# BYPASS_BLOCK.net
KiCad netlist of a schematic drawn in Altium Designer
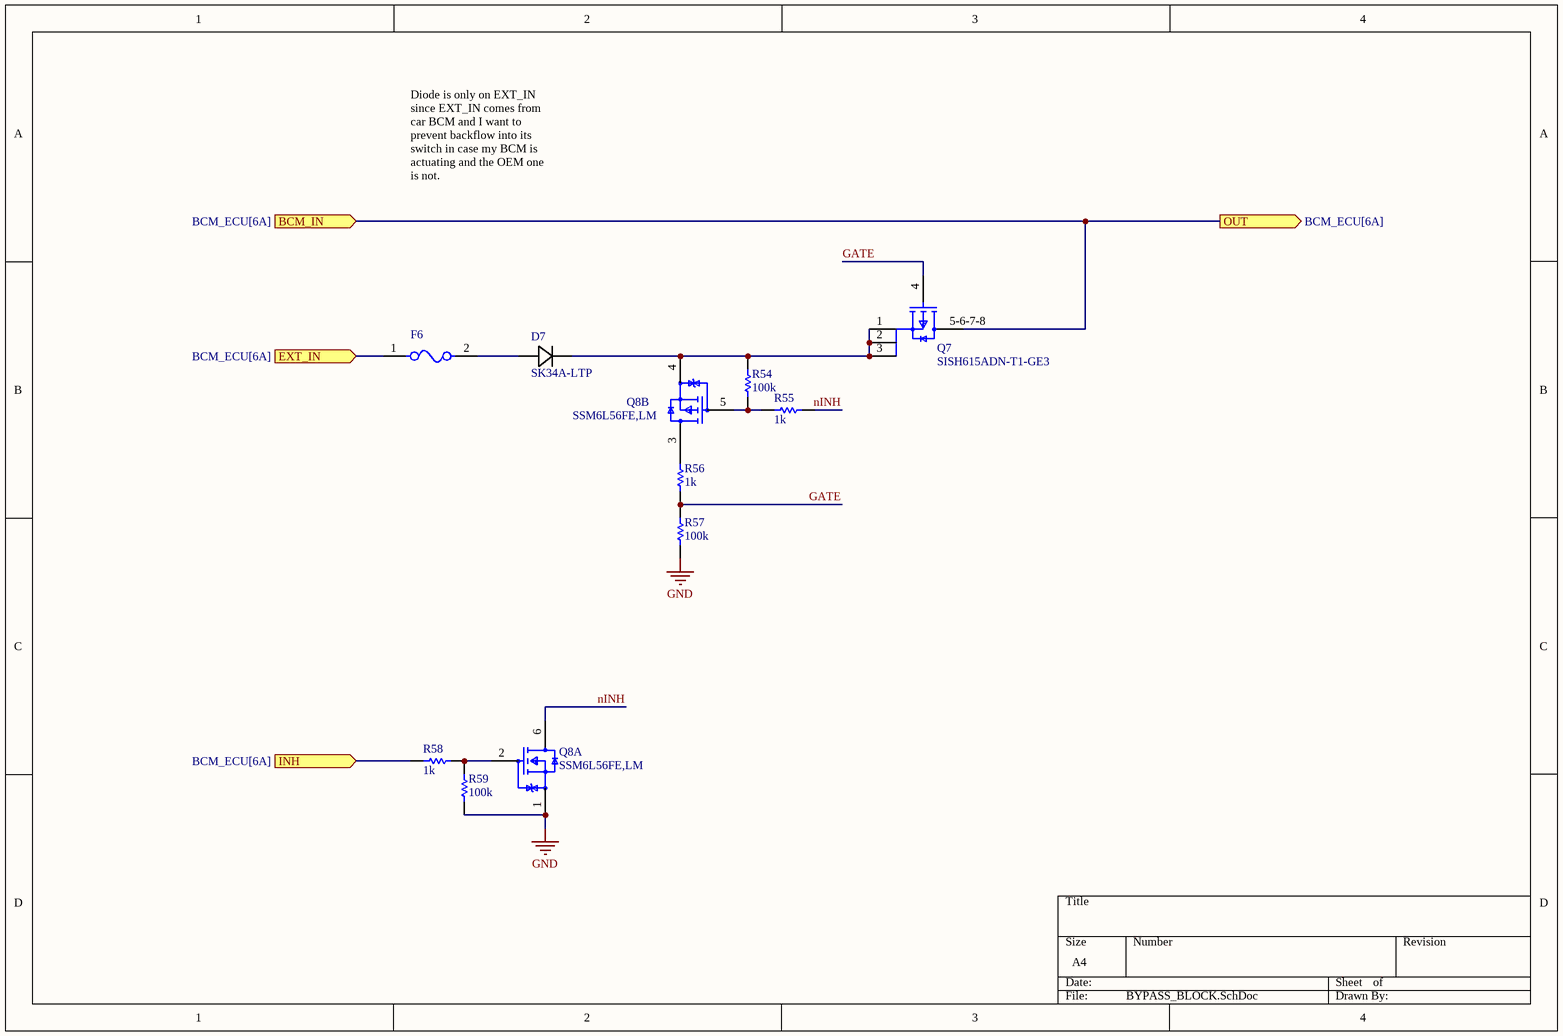
[diagram p0: BYPASS_BLOCK.SchDoc]

(export (version "E")
  (design (tool "Eeschema 10.0.6"))
  (components
    (comp (ref "D7")
      (value "SK34A-LTP")
      (footprint "SK34A-LTP-Footprint-1")
      (description "Rectifier Diode, Schottky, 1 Phase, 1 Element, 3A, 40V V(RRM), Silicon, DO-214AC")
      (libsource (lib "Space Concordia") (part "SK34A-LTP"))
    )
    (comp (ref "F6")
      (value "0466003.NR")
      (footprint "FP-0466-MFG")
      (description "FUSE BOARD MNT 3A 32VAC/VDC 1206")
      (fields
        (field (name "OCTOPART") "https://octopart.com/0466003.nr-littelfuse-565175")
        (field (name "MANUFACTURER") "Littelfuse")
      )
      (libsource (lib "Altium Content Vault") (part "5bcf9b9f640e542cf0359d10258e979"))
    )
    (comp (ref "Q7")
      (value "SISH615ADN-T1-GE3")
      (footprint "SISH615ADN-T1-GE3-Footprint-1")
      (description "Trans MOSFET P-CH 20V 22.1A 8-Pin PowerPAK 1212 EP T/R")
      (libsource (lib "Space Concordia") (part "CMP-013-00036-4"))
    )
    (comp (ref "Q8")
      (value "SSM6L56FE,LM")
      (footprint "FP-SON6-P-0_50-MFG")
      (description "SMALL-SIGNAL MOSFET 2 IN 1 NCH +")
      (libsource (lib "Altium Content Vault") (part "1a64cdd3a4d654d64722bb0a8ffcdea"))
    )
    (comp (ref "R54")
      (value "100k")
      (footprint "R0603B")
      (description "Resistor")
      (libsource (lib "Space Concordia") (part "Resistor"))
    )
    (comp (ref "R55")
      (value "1k")
      (footprint "R0603B")
      (description "Resistor")
      (libsource (lib "Space Concordia") (part "Resistor"))
    )
    (comp (ref "R56")
      (value "1k")
      (footprint "R0603B")
      (description "Resistor")
      (libsource (lib "Space Concordia") (part "Resistor"))
    )
    (comp (ref "R57")
      (value "100k")
      (footprint "R0603B")
      (description "Resistor")
      (libsource (lib "Space Concordia") (part "Resistor"))
    )
    (comp (ref "R58")
      (value "1k")
      (footprint "R0603B")
      (description "Resistor")
      (libsource (lib "Space Concordia") (part "Resistor"))
    )
    (comp (ref "R59")
      (value "100k")
      (footprint "R0603B")
      (description "Resistor")
      (libsource (lib "Space Concordia") (part "Resistor"))
    )
  )
  (nets
    (net (code "1") (name "/BCM_IN") (class "Default")
      (node (ref "Q7") (pin "5-6-7-8") (pinfunction "D_5-6-7-8") (pintype "passive"))
    )
    (net (code "2") (name "/EXT_IN") (class "Default")
      (node (ref "F6") (pin "1") (pinfunction "1_1") (pintype "passive"))
    )
    (net (code "3") (name "/GATE") (class "Default")
      (node (ref "Q7") (pin "4") (pinfunction "G_4") (pintype "passive"))
      (node (ref "R56") (pin "2") (pinfunction "2_2") (pintype "passive"))
      (node (ref "R57") (pin "1") (pinfunction "1_1") (pintype "passive"))
    )
    (net (code "4") (name "/INH") (class "Default")
      (node (ref "R58") (pin "2") (pinfunction "2_2") (pintype "passive"))
    )
    (net (code "5") (name "/nINH") (class "Default")
      (node (ref "Q8") (pin "6") (pinfunction "Drain_1_6") (pintype "passive"))
      (node (ref "R55") (pin "2") (pinfunction "2_2") (pintype "passive"))
    )
    (net (code "6") (name "GND") (class "Default")
      (node (ref "Q8") (pin "1") (pinfunction "Source_1_1") (pintype "passive"))
      (node (ref "R57") (pin "2") (pinfunction "2_2") (pintype "passive"))
      (node (ref "R59") (pin "1") (pinfunction "1_1") (pintype "passive"))
    )
    (net (code "7") (name "Net-(D7-ANODE)") (class "Default")
      (node (ref "D7") (pin "2") (pinfunction "ANODE_2") (pintype "passive"))
      (node (ref "F6") (pin "2") (pinfunction "2_2") (pintype "passive"))
    )
    (net (code "8") (name "Net-(D7-CATHODE)") (class "Default")
      (node (ref "D7") (pin "1") (pinfunction "CATHODE_1") (pintype "passive"))
      (node (ref "Q7") (pin "1") (pinfunction "S_1") (pintype "passive"))
      (node (ref "Q7") (pin "2") (pinfunction "S_2") (pintype "passive"))
      (node (ref "Q7") (pin "3") (pinfunction "S_3") (pintype "passive"))
      (node (ref "Q8") (pin "4") (pinfunction "Source_2_4") (pintype "passive"))
      (node (ref "R54") (pin "1") (pinfunction "1_1") (pintype "passive"))
    )
    (net (code "9") (name "Net-(Q8A-Gate_1)") (class "Default")
      (node (ref "Q8") (pin "2") (pinfunction "Gate_1_2") (pintype "passive"))
      (node (ref "R58") (pin "1") (pinfunction "1_1") (pintype "passive"))
      (node (ref "R59") (pin "2") (pinfunction "2_2") (pintype "passive"))
    )
    (net (code "10") (name "Net-(Q8B-Drain_2)") (class "Default")
      (node (ref "Q8") (pin "3") (pinfunction "Drain_2_3") (pintype "passive"))
      (node (ref "R56") (pin "1") (pinfunction "1_1") (pintype "passive"))
    )
    (net (code "11") (name "Net-(Q8B-Gate_2)") (class "Default")
      (node (ref "Q8") (pin "5") (pinfunction "Gate_2_5") (pintype "passive"))
      (node (ref "R54") (pin "2") (pinfunction "2_2") (pintype "passive"))
      (node (ref "R55") (pin "1") (pinfunction "1_1") (pintype "passive"))
    )
  )
)
